# Adafruit_Feather_M0_Basic_rev_C.net
KiCad netlist of a schematic drawn in Altium Designer
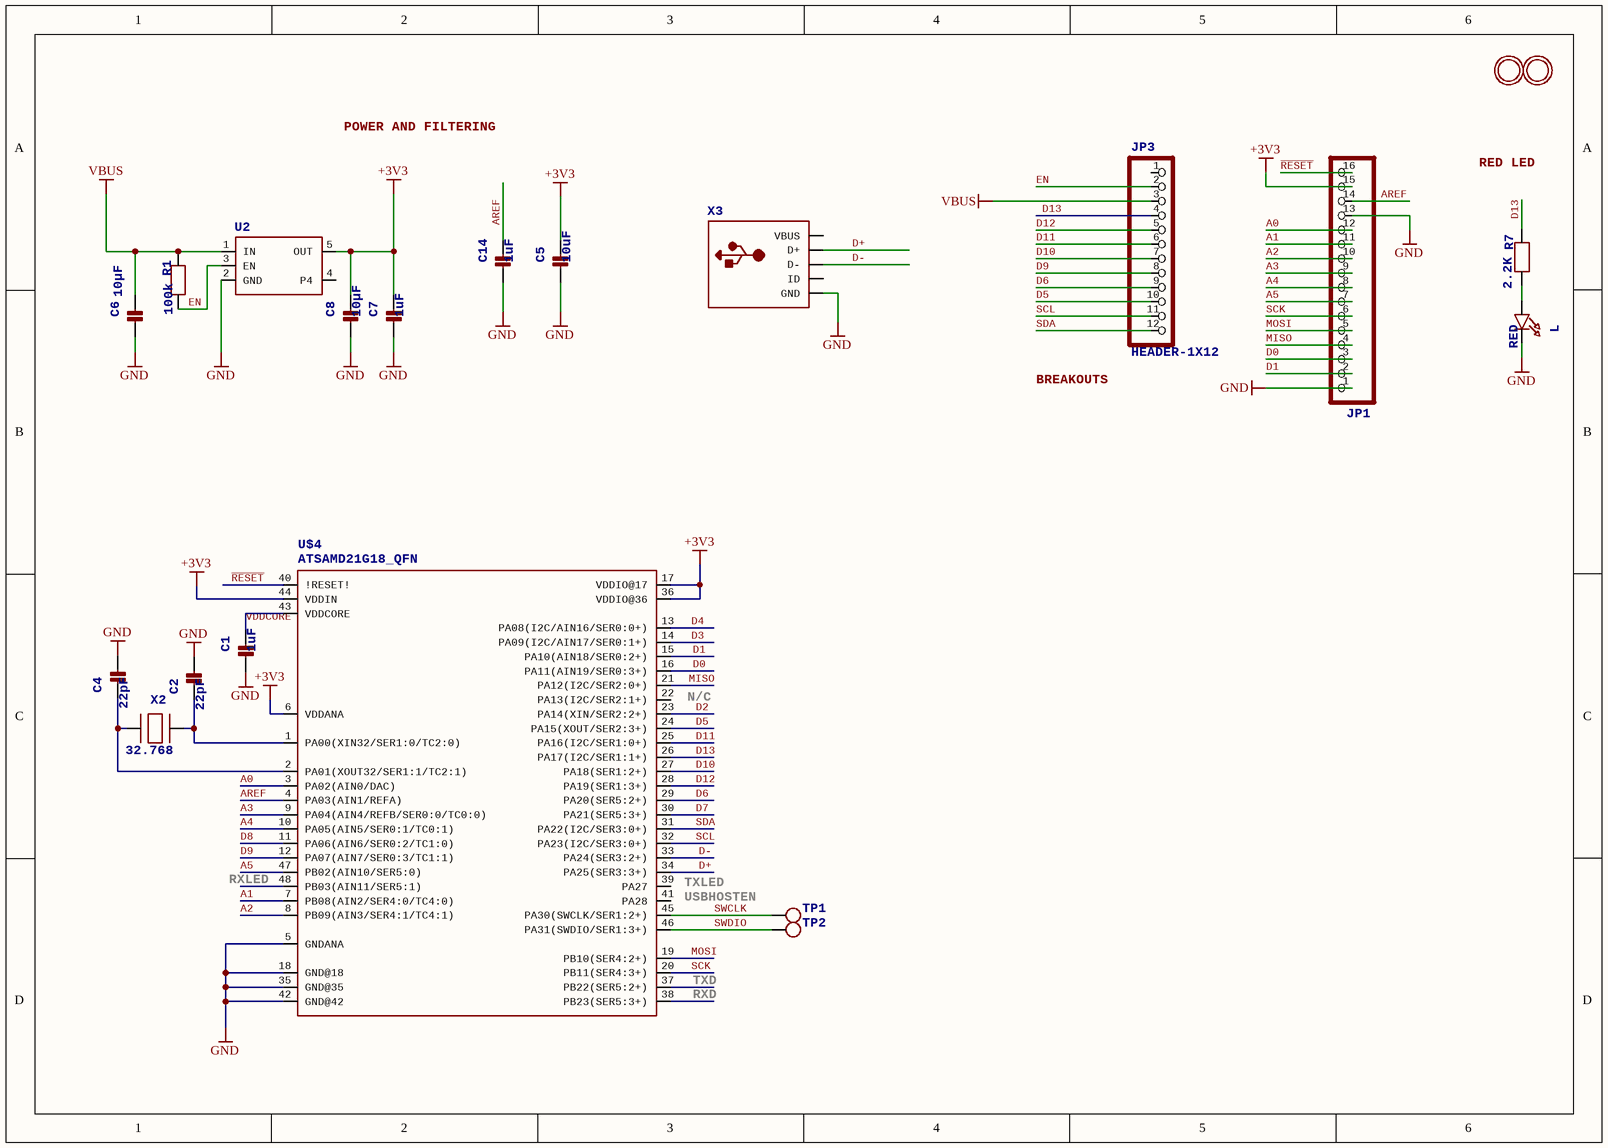
[diagram p0: Adafruit Feather M0 Basic rev C.SchDoc]

(export (version "E")
  (design (tool "Eeschema 10.0.6"))
  (components
    (comp (ref "C1")
      (value "1uF")
      (footprint "0603-NO")
      (libsource (lib "microbuilder") (part "CAP_CERAMIC0603_NO"))
    )
    (comp (ref "C2") (value "22pF") (footprint "0603-NO") (libsource (lib "") (part "CAP_CERAMIC0603_NO_1")))
    (comp (ref "C4") (value "22pF") (footprint "0603-NO") (libsource (lib "") (part "CAP_CERAMIC0603_NO_1")))
    (comp (ref "C5")
      (value "10uF")
      (footprint "0805-NO")
      (libsource (lib "microbuilder") (part "CAP_CERAMIC0805-NOOUTLINE"))
    )
    (comp (ref "C6")
      (value "10µF")
      (footprint "0805-NO")
      (libsource (lib "microbuilder") (part "CAP_CERAMIC0805-NOOUTLINE"))
    )
    (comp (ref "C7")
      (value "1uF")
      (footprint "0603-NO")
      (libsource (lib "microbuilder") (part "CAP_CERAMIC0603_NO"))
    )
    (comp (ref "C8")
      (value "10µF")
      (footprint "0805-NO")
      (libsource (lib "microbuilder") (part "CAP_CERAMIC0805-NOOUTLINE"))
    )
    (comp (ref "C14")
      (value "1uF")
      (footprint "0603-NO")
      (libsource (lib "microbuilder") (part "CAP_CERAMIC0603_NO"))
    )
    (comp (ref "JP1")
      (value "HEADER-1X16ROUND")
      (footprint "1X16_ROUND")
      (description "<b>PIN HEADER</b>")
      (libsource (lib "microbuilder") (part "HEADER-1X16ROUND"))
    )
    (comp (ref "JP3")
      (value "HEADER-1X12")
      (footprint "1X12_ROUND")
      (libsource (lib "microbuilder") (part "HEADER-1X12"))
    )
    (comp (ref "L")
      (value "RED")
      (footprint "CHIPLED_0805_NOOUTLINE")
      (libsource (lib "microbuilder") (part "LED0805_NOOUTLINE"))
    )
    (comp (ref "R1")
      (value "100k")
      (footprint "0603-NO")
      (libsource (lib "microbuilder") (part "RESISTOR_0603_NOOUT"))
    )
    (comp (ref "R7")
      (value "2.2K")
      (footprint "0603-NO")
      (libsource (lib "microbuilder") (part "RESISTOR_0603_NOOUT"))
    )
    (comp (ref "TP1")
      (value "~")
      (footprint "TESTPOINT_ROUND_1.5MM")
      (libsource (lib "microbuilder") (part "TESTPOINTROUND1.5MM"))
    )
    (comp (ref "TP2")
      (value "~")
      (footprint "TESTPOINT_ROUND_1.5MM")
      (libsource (lib "microbuilder") (part "TESTPOINTROUND1.5MM"))
    )
    (comp (ref "U$4")
      (value "ATSAMD21G18_QFN")
      (footprint "QFN-48")
      (libsource (lib "samd21-temp") (part "ATSAMD21G-M"))
    )
    (comp (ref "U$31")
      (value "MOUNTINGHOLE2.5")
      (footprint "MOUNTINGHOLE_2.5_PLATED")
      (description "<b>Mounting Hole</b>\n<p>For #2 screws (0.086\"/2.18mm width, 0.094\"/2.4mm hole) use 2.5mm</p>")
      (libsource (lib "microbuilder") (part "MOUNTINGHOLE2.5"))
    )
    (comp (ref "U$32")
      (value "MOUNTINGHOLE2.5")
      (footprint "MOUNTINGHOLE_2.5_PLATED")
      (description "<b>Mounting Hole</b>\n<p>For #2 screws (0.086\"/2.18mm width, 0.094\"/2.4mm hole) use 2.5mm</p>")
      (libsource (lib "microbuilder") (part "MOUNTINGHOLE2.5"))
    )
    (comp (ref "U2") (value "~") (footprint "SOT23-5") (libsource (lib "microbuilder") (part "VREG_SOT23-5")))
    (comp (ref "X2")
      (value "32.768")
      (footprint "XTAL3215")
      (description "Low cost SMT crystals, no capacitors included\n<p>http://www.ladyada.net/library/eagle</p>")
      (libsource (lib "adafruit2") (part "XTAL-3.2X1.5"))
    )
    (comp (ref "X3") (value "~") (footprint "USB-MINIB") (libsource (lib "adafruit") (part "USBMINIB")))
  )
  (nets
    (net (code "1") (name "+3V3") (class "Default")
      (node (ref "C5") (pin "1") (pinfunction "1_1") (pintype "passive"))
      (node (ref "C7") (pin "1") (pinfunction "1_1") (pintype "passive"))
      (node (ref "C8") (pin "1") (pinfunction "1_1") (pintype "passive"))
      (node (ref "JP1") (pin "15") (pinfunction "15_15") (pintype "passive"))
      (node (ref "U$4") (pin "17") (pinfunction "VDDIO@17_17") (pintype "passive"))
      (node (ref "U$4") (pin "36") (pinfunction "VDDIO@36_36") (pintype "passive"))
      (node (ref "U$4") (pin "44") (pinfunction "VDDIN_44") (pintype "passive"))
      (node (ref "U$4") (pin "6") (pinfunction "VDDANA_6") (pintype "passive"))
      (node (ref "U2") (pin "5") (pinfunction "OUT_5") (pintype "passive"))
    )
    (net (code "2") (name "/A0") (class "Default")
      (node (ref "JP1") (pin "12") (pinfunction "12_12") (pintype "passive"))
      (node (ref "U$4") (pin "3") (pinfunction "PA02(AIN0/DAC)_3") (pintype "passive"))
    )
    (net (code "3") (name "/A1") (class "Default")
      (node (ref "JP1") (pin "11") (pinfunction "11_11") (pintype "passive"))
      (node (ref "U$4") (pin "7") (pinfunction "PB08(AIN2/SER4:0/TC4:0)_7") (pintype "passive"))
    )
    (net (code "4") (name "/A2") (class "Default")
      (node (ref "JP1") (pin "10") (pinfunction "10_10") (pintype "passive"))
      (node (ref "U$4") (pin "8") (pinfunction "PB09(AIN3/SER4:1/TC4:1)_8") (pintype "passive"))
    )
    (net (code "5") (name "/A3") (class "Default")
      (node (ref "JP1") (pin "9") (pinfunction "9_9") (pintype "passive"))
      (node (ref "U$4") (pin "9") (pinfunction "PA04(AIN4/REFB/SER0:0/TC0:0)_9") (pintype "passive"))
    )
    (net (code "6") (name "/A4") (class "Default")
      (node (ref "JP1") (pin "8") (pinfunction "8_8") (pintype "passive"))
      (node (ref "U$4") (pin "10") (pinfunction "PA05(AIN5/SER0:1/TC0:1)_10") (pintype "passive"))
    )
    (net (code "7") (name "/A5") (class "Default")
      (node (ref "JP1") (pin "7") (pinfunction "7_7") (pintype "passive"))
      (node (ref "U$4") (pin "47") (pinfunction "PB02(AIN10/SER5:0)_47") (pintype "passive"))
    )
    (net (code "8") (name "/AREF") (class "Default")
      (node (ref "C14") (pin "1") (pinfunction "1_1") (pintype "passive"))
      (node (ref "JP1") (pin "14") (pinfunction "14_14") (pintype "passive"))
      (node (ref "U$4") (pin "4") (pinfunction "PA03(AIN1/REFA)_4") (pintype "passive"))
    )
    (net (code "9") (name "/D+") (class "Default")
      (node (ref "U$4") (pin "34") (pinfunction "PA25(SER3:3+)_34") (pintype "passive"))
      (node (ref "X3") (pin "D+") (pinfunction "D+_D+") (pintype "passive"))
    )
    (net (code "10") (name "/D-") (class "Default")
      (node (ref "U$4") (pin "33") (pinfunction "PA24(SER3:2+)_33") (pintype "passive"))
      (node (ref "X3") (pin "D-") (pinfunction "D-_D-") (pintype "passive"))
    )
    (net (code "11") (name "/D0") (class "Default")
      (node (ref "JP1") (pin "3") (pinfunction "3_3") (pintype "passive"))
      (node (ref "U$4") (pin "16") (pinfunction "PA11(AIN19/SER0:3+)_16") (pintype "passive"))
    )
    (net (code "12") (name "/D1") (class "Default")
      (node (ref "JP1") (pin "2") (pinfunction "2_2") (pintype "passive"))
      (node (ref "U$4") (pin "15") (pinfunction "PA10(AIN18/SER0:2+)_15") (pintype "passive"))
    )
    (net (code "13") (name "/D2") (class "Default")
      (node (ref "U$4") (pin "23") (pinfunction "PA14(XIN/SER2:2+)_23") (pintype "passive"))
    )
    (net (code "14") (name "/D3") (class "Default")
      (node (ref "U$4") (pin "14") (pinfunction "PA09(I2C/AIN17/SER0:1+)_14") (pintype "passive"))
    )
    (net (code "15") (name "/D4") (class "Default")
      (node (ref "U$4") (pin "13") (pinfunction "PA08(I2C/AIN16/SER0:0+)_13") (pintype "passive"))
    )
    (net (code "16") (name "/D5") (class "Default")
      (node (ref "JP3") (pin "10") (pinfunction "10_10") (pintype "passive"))
      (node (ref "U$4") (pin "24") (pinfunction "PA15(XOUT/SER2:3+)_24") (pintype "passive"))
    )
    (net (code "17") (name "/D6") (class "Default")
      (node (ref "JP3") (pin "9") (pinfunction "9_9") (pintype "passive"))
      (node (ref "U$4") (pin "29") (pinfunction "PA20(SER5:2+)_29") (pintype "passive"))
    )
    (net (code "18") (name "/D7") (class "Default")
      (node (ref "U$4") (pin "30") (pinfunction "PA21(SER5:3+)_30") (pintype "passive"))
    )
    (net (code "19") (name "/D8") (class "Default")
      (node (ref "U$4") (pin "11") (pinfunction "PA06(AIN6/SER0:2/TC1:0)_11") (pintype "passive"))
    )
    (net (code "20") (name "/D9") (class "Default")
      (node (ref "JP3") (pin "8") (pinfunction "8_8") (pintype "passive"))
      (node (ref "U$4") (pin "12") (pinfunction "PA07(AIN7/SER0:3/TC1:1)_12") (pintype "passive"))
    )
    (net (code "21") (name "/D10") (class "Default")
      (node (ref "JP3") (pin "7") (pinfunction "7_7") (pintype "passive"))
      (node (ref "U$4") (pin "27") (pinfunction "PA18(SER1:2+)_27") (pintype "passive"))
    )
    (net (code "22") (name "/D11") (class "Default")
      (node (ref "JP3") (pin "6") (pinfunction "6_6") (pintype "passive"))
      (node (ref "U$4") (pin "25") (pinfunction "PA16(I2C/SER1:0+)_25") (pintype "passive"))
    )
    (net (code "23") (name "/D12") (class "Default")
      (node (ref "JP3") (pin "5") (pinfunction "5_5") (pintype "passive"))
      (node (ref "U$4") (pin "28") (pinfunction "PA19(SER1:3+)_28") (pintype "passive"))
    )
    (net (code "24") (name "/D13") (class "Default")
      (node (ref "JP3") (pin "4") (pinfunction "4_4") (pintype "passive"))
      (node (ref "R7") (pin "1") (pinfunction "1_1") (pintype "passive"))
      (node (ref "U$4") (pin "26") (pinfunction "PA17(I2C/SER1:1+)_26") (pintype "passive"))
    )
    (net (code "25") (name "/EN") (class "Default")
      (node (ref "JP3") (pin "2") (pinfunction "2_2") (pintype "passive"))
      (node (ref "R1") (pin "2") (pinfunction "2_2") (pintype "passive"))
      (node (ref "U2") (pin "3") (pinfunction "EN_3") (pintype "passive"))
    )
    (net (code "26") (name "/MISO") (class "Default")
      (node (ref "JP1") (pin "4") (pinfunction "4_4") (pintype "passive"))
      (node (ref "U$4") (pin "21") (pinfunction "PA12(I2C/SER2:0+)_21") (pintype "passive"))
    )
    (net (code "27") (name "/MOSI") (class "Default")
      (node (ref "JP1") (pin "5") (pinfunction "5_5") (pintype "passive"))
      (node (ref "U$4") (pin "19") (pinfunction "PB10(SER4:2+)_19") (pintype "passive"))
    )
    (net (code "28") (name "/SCK") (class "Default")
      (node (ref "JP1") (pin "6") (pinfunction "6_6") (pintype "passive"))
      (node (ref "U$4") (pin "20") (pinfunction "PB11(SER4:3+)_20") (pintype "passive"))
    )
    (net (code "29") (name "/SCL") (class "Default")
      (node (ref "JP3") (pin "11") (pinfunction "11_11") (pintype "passive"))
      (node (ref "U$4") (pin "32") (pinfunction "PA23(I2C/SER3:0+)_32") (pintype "passive"))
    )
    (net (code "30") (name "/SDA") (class "Default")
      (node (ref "JP3") (pin "12") (pinfunction "12_12") (pintype "passive"))
      (node (ref "U$4") (pin "31") (pinfunction "PA22(I2C/SER3:0+)_31") (pintype "passive"))
    )
    (net (code "31") (name "/SWCLK") (class "Default")
      (node (ref "TP1") (pin "P$1") (pinfunction "P$1_P$1") (pintype "passive"))
      (node (ref "U$4") (pin "45") (pinfunction "PA30(SWCLK/SER1:2+)_45") (pintype "passive"))
    )
    (net (code "32") (name "/SWDIO") (class "Default")
      (node (ref "TP2") (pin "P$1") (pinfunction "P$1_P$1") (pintype "passive"))
      (node (ref "U$4") (pin "46") (pinfunction "PA31(SWDIO/SER1:3+)_46") (pintype "passive"))
    )
    (net (code "33") (name "/VDDCORE") (class "Default")
      (node (ref "C1") (pin "1") (pinfunction "1_1") (pintype "passive"))
      (node (ref "U$4") (pin "43") (pinfunction "VDDCORE_43") (pintype "passive"))
    )
    (net (code "34") (name "/~{RESET}") (class "Default")
      (node (ref "JP1") (pin "16") (pinfunction "16_16") (pintype "passive"))
      (node (ref "U$4") (pin "40") (pinfunction "!RESET!_40") (pintype "passive"))
    )
    (net (code "35") (name "GND") (class "Default")
      (node (ref "C1") (pin "2") (pinfunction "2_2") (pintype "passive"))
      (node (ref "C14") (pin "2") (pinfunction "2_2") (pintype "passive"))
      (node (ref "C2") (pin "2") (pinfunction "2_2") (pintype "passive"))
      (node (ref "C4") (pin "2") (pinfunction "2_2") (pintype "passive"))
      (node (ref "C5") (pin "2") (pinfunction "2_2") (pintype "passive"))
      (node (ref "C6") (pin "2") (pinfunction "2_2") (pintype "passive"))
      (node (ref "C7") (pin "2") (pinfunction "2_2") (pintype "passive"))
      (node (ref "C8") (pin "2") (pinfunction "2_2") (pintype "passive"))
      (node (ref "JP1") (pin "1") (pinfunction "1_1") (pintype "passive"))
      (node (ref "JP1") (pin "13") (pinfunction "13_13") (pintype "passive"))
      (node (ref "L") (pin "C") (pinfunction "C_C") (pintype "passive"))
      (node (ref "U$4") (pin "18") (pinfunction "GND@18_18") (pintype "passive"))
      (node (ref "U$4") (pin "35") (pinfunction "GND@35_35") (pintype "passive"))
      (node (ref "U$4") (pin "42") (pinfunction "GND@42_42") (pintype "passive"))
      (node (ref "U$4") (pin "5") (pinfunction "GNDANA_5") (pintype "passive"))
      (node (ref "U2") (pin "2") (pinfunction "GND_2") (pintype "passive"))
      (node (ref "X3") (pin "GND") (pinfunction "GND_GND") (pintype "power_in"))
    )
    (net (code "36") (name "Net-(L-PadA)") (class "Default")
      (node (ref "L") (pin "A") (pinfunction "A_A") (pintype "passive"))
      (node (ref "R7") (pin "2") (pinfunction "2_2") (pintype "passive"))
    )
    (net (code "37") (name "Net-(U$4-PA00(XIN32{slash}SER1:0{slash}TC2:0))") (class "Default")
      (node (ref "C2") (pin "1") (pinfunction "1_1") (pintype "passive"))
      (node (ref "U$4") (pin "1") (pinfunction "PA00(XIN32/SER1:0/TC2:0)_1") (pintype "passive"))
      (node (ref "X2") (pin "P$1") (pinfunction "P$1_P$1") (pintype "passive"))
    )
    (net (code "38") (name "Net-(U$4-PA01(XOUT32{slash}SER1:1{slash}TC2:1))") (class "Default")
      (node (ref "C4") (pin "1") (pinfunction "1_1") (pintype "passive"))
      (node (ref "U$4") (pin "2") (pinfunction "PA01(XOUT32/SER1:1/TC2:1)_2") (pintype "passive"))
      (node (ref "X2") (pin "P$2") (pinfunction "P$2_P$2") (pintype "passive"))
    )
    (net (code "39") (name "VBUS") (class "Default")
      (node (ref "C6") (pin "1") (pinfunction "1_1") (pintype "passive"))
      (node (ref "JP3") (pin "3") (pinfunction "3_3") (pintype "passive"))
      (node (ref "R1") (pin "1") (pinfunction "1_1") (pintype "passive"))
      (node (ref "U2") (pin "1") (pinfunction "IN_1") (pintype "passive"))
    )
    (net (code "40") (name "unconnected-(JP3-Pad1)") (class "Default")
      (node (ref "JP3") (pin "1") (pinfunction "1_1") (pintype "passive"))
    )
    (net (code "41") (name "unconnected-(U$4-PA13(I2C{slash}SER2:1+)-Pad22)") (class "Default")
      (node (ref "U$4") (pin "22") (pinfunction "PA13(I2C/SER2:1+)_22") (pintype "passive"))
    )
    (net (code "42") (name "unconnected-(U$4-PA27-Pad39)") (class "Default")
      (node (ref "U$4") (pin "39") (pinfunction "PA27_39") (pintype "passive"))
    )
    (net (code "43") (name "unconnected-(U$4-PA28-Pad41)") (class "Default")
      (node (ref "U$4") (pin "41") (pinfunction "PA28_41") (pintype "passive"))
    )
    (net (code "44") (name "unconnected-(U$4-PB03(AIN11{slash}SER5:1)-Pad48)") (class "Default")
      (node (ref "U$4") (pin "48") (pinfunction "PB03(AIN11/SER5:1)_48") (pintype "passive"))
    )
    (net (code "45") (name "unconnected-(U$4-PB22(SER5:2+)-Pad37)") (class "Default")
      (node (ref "U$4") (pin "37") (pinfunction "PB22(SER5:2+)_37") (pintype "passive"))
    )
    (net (code "46") (name "unconnected-(U$4-PB23(SER5:3+)-Pad38)") (class "Default")
      (node (ref "U$4") (pin "38") (pinfunction "PB23(SER5:3+)_38") (pintype "passive"))
    )
    (net (code "47") (name "unconnected-(U2-P4-Pad4)") (class "Default")
      (node (ref "U2") (pin "4") (pinfunction "P4_4") (pintype "passive"))
    )
    (net (code "48") (name "unconnected-(X3-PadID)") (class "Default")
      (node (ref "X3") (pin "ID") (pinfunction "ID_ID") (pintype "passive"))
    )
    (net (code "49") (name "unconnected-(X3-PadVBUS)") (class "Default")
      (node (ref "X3") (pin "VBUS") (pinfunction "VBUS_VBUS") (pintype "power_in"))
    )
  )
)
